# SY8120B1ABC.net
KiCad netlist of a schematic drawn in Altium Designer
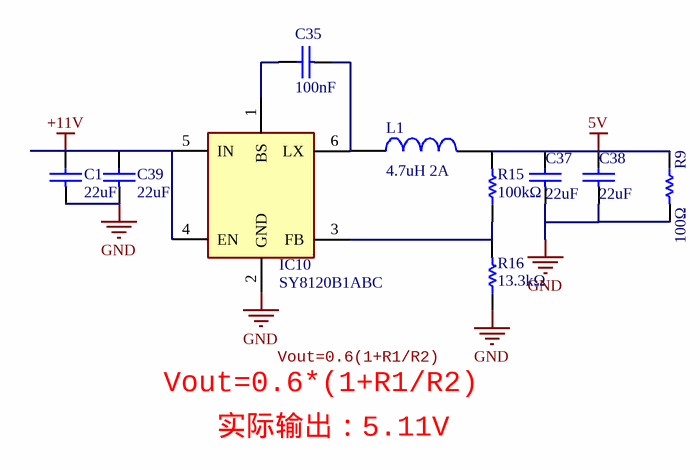
[diagram p0: SY8120B1ABC.SchDoc]

(export (version "E")
  (design (tool "Eeschema 10.0.6"))
  (components
    (comp (ref "C1")
      (value "22uF")
      (footprint "C_0805")
      (description "贴片电容")
      (libsource (lib "IntLib-Passive") (part "Cap_Chip"))
    )
    (comp (ref "C35")
      (value "100nF")
      (footprint "C_0402")
      (description "贴片电容")
      (libsource (lib "IntLib-Passive") (part "Cap_Chip"))
    )
    (comp (ref "C37")
      (value "22uF")
      (footprint "C_0805")
      (description "贴片电容")
      (libsource (lib "IntLib-Passive") (part "Cap_Chip"))
    )
    (comp (ref "C38")
      (value "22uF")
      (footprint "C_0805")
      (description "贴片电容")
      (libsource (lib "IntLib-Passive") (part "Cap_Chip"))
    )
    (comp (ref "C39")
      (value "22uF")
      (footprint "C_0805")
      (description "贴片电容")
      (libsource (lib "IntLib-Passive") (part "Cap_Chip"))
    )
    (comp (ref "IC10")
      (value "SY8120B1ABC")
      (footprint "SOT23-6")
      (description "DC-DC芯片")
      (libsource (lib "电源芯片") (part "SY8120B1ABC"))
    )
    (comp (ref "L1")
      (value "4.7uH 2A")
      (footprint "CD32")
      (description "INDUCTOR")
      (libsource (lib "电感") (part "INDUCTOR"))
    )
    (comp (ref "R9")
      (value "100Ω")
      (footprint "R_0805")
      (description "贴片电阻")
      (libsource (lib "IntLib-Passive") (part "Res_Chip"))
    )
    (comp (ref "R15")
      (value "100kΩ")
      (footprint "R_0402")
      (description "贴片电阻")
      (libsource (lib "IntLib-Passive") (part "Res_Chip"))
    )
    (comp (ref "R16")
      (value "13.3kΩ")
      (footprint "R_0402")
      (description "贴片电阻")
      (libsource (lib "IntLib-Passive") (part "Res_Chip"))
    )
  )
  (nets
    (net (code "1") (name "+11V") (class "Default")
      (node (ref "C1") (pin "2") (pinfunction "2_2") (pintype "passive"))
      (node (ref "C39") (pin "2") (pinfunction "2_2") (pintype "passive"))
      (node (ref "IC10") (pin "4") (pinfunction "EN_4") (pintype "passive"))
      (node (ref "IC10") (pin "5") (pinfunction "IN_5") (pintype "passive"))
    )
    (net (code "2") (name "5V") (class "Default")
      (node (ref "C37") (pin "2") (pinfunction "2_2") (pintype "passive"))
      (node (ref "C38") (pin "2") (pinfunction "2_2") (pintype "passive"))
      (node (ref "L1") (pin "2") (pinfunction "2_2") (pintype "passive"))
      (node (ref "R15") (pin "2") (pinfunction "2_2") (pintype "passive"))
      (node (ref "R9") (pin "1") (pinfunction "1_1") (pintype "passive"))
    )
    (net (code "3") (name "GND") (class "Default")
      (node (ref "C1") (pin "1") (pinfunction "1_1") (pintype "passive"))
      (node (ref "C37") (pin "1") (pinfunction "1_1") (pintype "passive"))
      (node (ref "C38") (pin "1") (pinfunction "1_1") (pintype "passive"))
      (node (ref "C39") (pin "1") (pinfunction "1_1") (pintype "passive"))
      (node (ref "IC10") (pin "2") (pinfunction "GND_2") (pintype "passive"))
      (node (ref "R16") (pin "1") (pinfunction "1_1") (pintype "passive"))
      (node (ref "R9") (pin "2") (pinfunction "2_2") (pintype "passive"))
    )
    (net (code "4") (name "Net-(IC10-BS)") (class "Default")
      (node (ref "C35") (pin "2") (pinfunction "2_2") (pintype "passive"))
      (node (ref "IC10") (pin "1") (pinfunction "BS_1") (pintype "passive"))
    )
    (net (code "5") (name "Net-(IC10-FB)") (class "Default")
      (node (ref "IC10") (pin "3") (pinfunction "FB_3") (pintype "passive"))
      (node (ref "R15") (pin "1") (pinfunction "1_1") (pintype "passive"))
      (node (ref "R16") (pin "2") (pinfunction "2_2") (pintype "passive"))
    )
    (net (code "6") (name "Net-(IC10-LX)") (class "Default")
      (node (ref "C35") (pin "1") (pinfunction "1_1") (pintype "passive"))
      (node (ref "IC10") (pin "6") (pinfunction "LX_6") (pintype "passive"))
      (node (ref "L1") (pin "1") (pinfunction "1_1") (pintype "passive"))
    )
  )
)
